# attenuator.net
KiCad netlist of a schematic drawn in Altium Designer
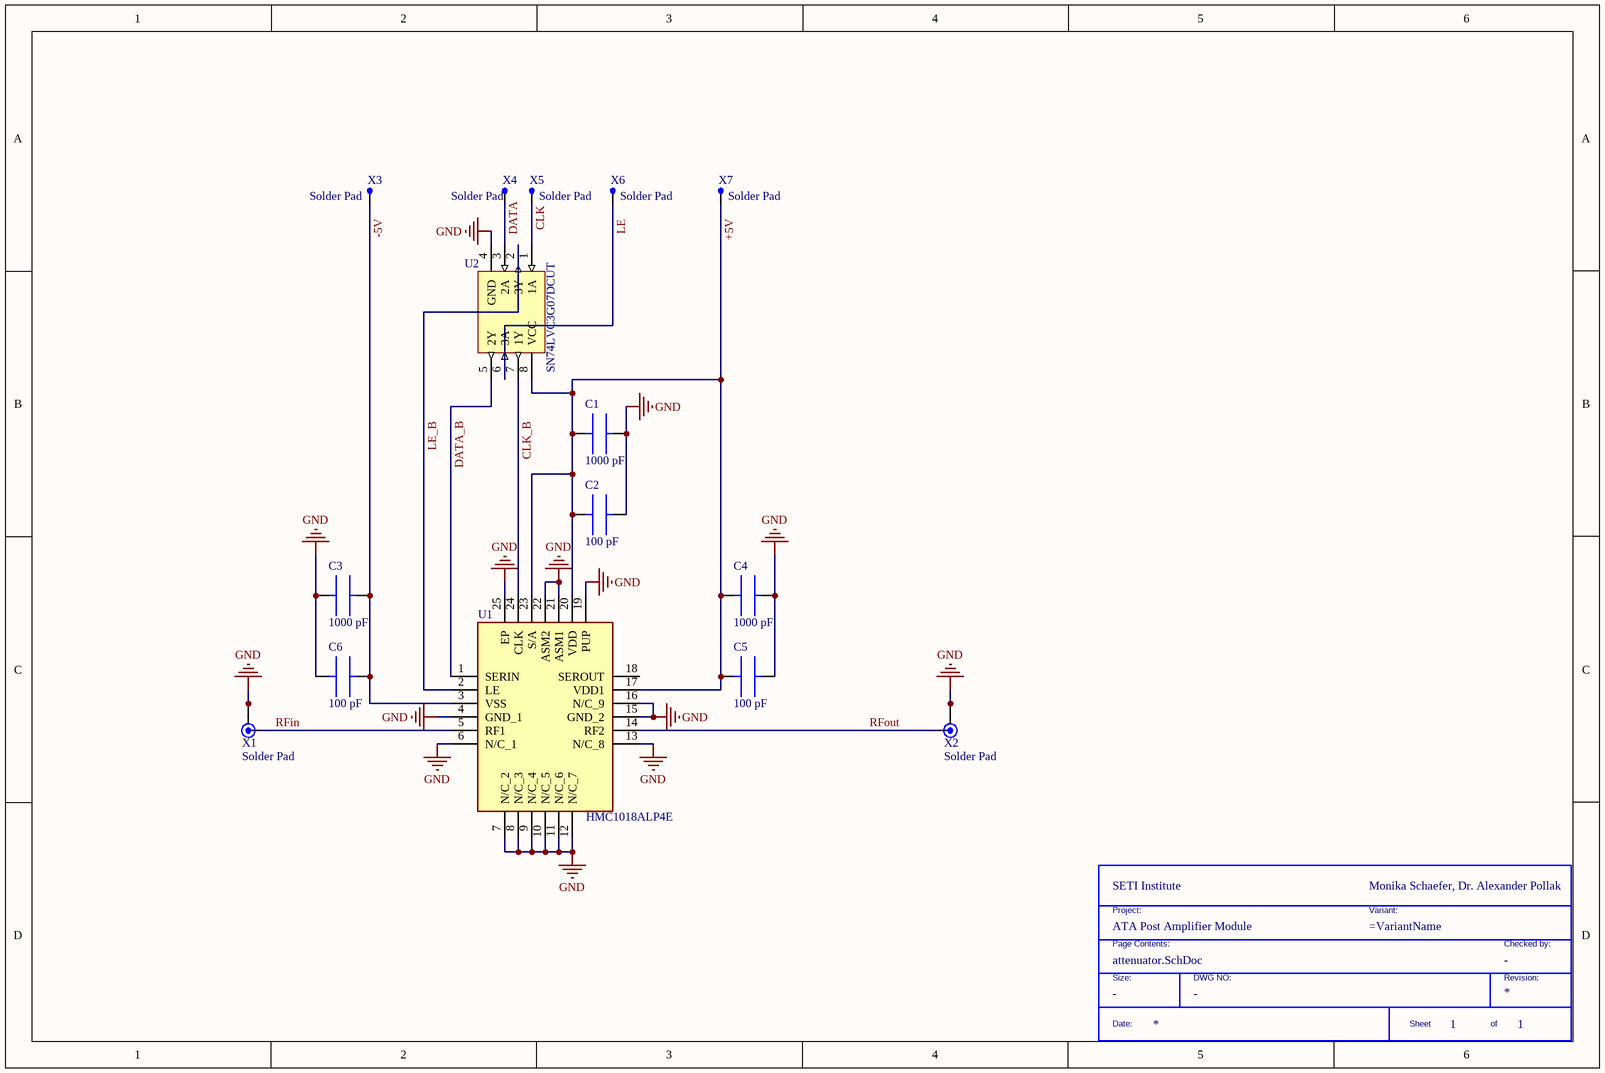
[diagram p0: attenuator.SchDoc]

(export (version "E")
  (design (tool "Eeschema 10.0.6"))
  (components
    (comp (ref "*")
      (value "TitleBlock")
      (description "Standard Title Block")
      (fields (field (name "DWG NO") "-") (field (name "SIZE") "-") (field (name "CHECKED BY") "-"))
      (libsource (lib "amp") (part "TitleBlock"))
    )
    (comp (ref "C1")
      (value "1000 pF")
      (footprint "C1000pF__C100nF")
      (fields
        (field (name "MANUFACTURER") "Murata")
        (field (name "MANUFACTURER PART NUMBER") "GCM1885C1H102FA16D")
      )
      (libsource (lib "attenuator") (part "C1000pF_GCM1885C1H102FA16D"))
    )
    (comp (ref "C2")
      (value "100 pF")
      (footprint "C100pF")
      (description "Multilayer Ceramic Capacitors MLCC - SMD/SMT 100 pF 100 VDC 1% 0402 C0G (NP0)")
      (fields
        (field (name "MANUFACTURER") "Murata")
        (field (name "MANUFACTURER PART NUMBER") "GRM1555C2A101FA01D")
      )
      (libsource (lib "attenuator") (part "C100pF_GRM1555C2A101FA01D"))
    )
    (comp (ref "C3")
      (value "1000 pF")
      (footprint "C1000pF__C100nF")
      (fields
        (field (name "MANUFACTURER") "Murata")
        (field (name "MANUFACTURER PART NUMBER") "GCM1885C1H102FA16D")
      )
      (libsource (lib "attenuator") (part "C1000pF_GCM1885C1H102FA16D"))
    )
    (comp (ref "C4")
      (value "1000 pF")
      (footprint "C1000pF__C100nF")
      (fields
        (field (name "MANUFACTURER") "Murata")
        (field (name "MANUFACTURER PART NUMBER") "GCM1885C1H102FA16D")
      )
      (libsource (lib "attenuator") (part "C1000pF_GCM1885C1H102FA16D"))
    )
    (comp (ref "C5")
      (value "100 pF")
      (footprint "C100pF")
      (description "Multilayer Ceramic Capacitors MLCC - SMD/SMT 100 pF 100 VDC 1% 0402 C0G (NP0)")
      (fields
        (field (name "MANUFACTURER") "Murata")
        (field (name "MANUFACTURER PART NUMBER") "GRM1555C2A101FA01D")
      )
      (libsource (lib "attenuator") (part "C100pF_GRM1555C2A101FA01D"))
    )
    (comp (ref "C6")
      (value "100 pF")
      (footprint "C100pF")
      (description "Multilayer Ceramic Capacitors MLCC - SMD/SMT 100 pF 100 VDC 1% 0402 C0G (NP0)")
      (fields
        (field (name "MANUFACTURER") "Murata")
        (field (name "MANUFACTURER PART NUMBER") "GRM1555C2A101FA01D")
      )
      (libsource (lib "attenuator") (part "C100pF_GRM1555C2A101FA01D"))
    )
    (comp (ref "U1")
      (value "HMC1018ALP4E")
      (footprint "Att_HMC101018ALPE")
      (description "Attenuators Attenuators")
      (fields (field (name "MOUSER PART NUMBER") "584-HMC1018ALP4E"))
      (libsource (lib "attenuator") (part "Att_HMC1018ALP4E"))
    )
    (comp (ref "U2")
      (value "SN74LVC3G07DCUT")
      (footprint "Buf_SN74LVC3G07DCUT")
      (description "Buffer, LVC/LCX/Z Series, 3-Func, 1-Input, CMOS, PDSO8")
      (fields (field (name "MANUFACTURER") "Texas Instruments"))
      (libsource (lib "attenuator") (part "Buf_SN74LVC3G07DCUT"))
    )
    (comp (ref "X1")
      (value "Solder Pad")
      (footprint "CPW Edge Connector")
      (description "Solder pad for RF Coplanar Waveguide Rogers 4350B Thickness 0.020\" Copper 1oz")
      (libsource (lib "amp") (part "RF  CPW Solder Pad"))
    )
    (comp (ref "X2")
      (value "Solder Pad")
      (footprint "CPW Edge Connector")
      (description "Solder pad for RF Coplanar Waveguide Rogers 4350B Thickness 0.020\" Copper 1oz")
      (libsource (lib "amp") (part "RF  CPW Solder Pad"))
    )
    (comp (ref "X3")
      (value "Solder Pad")
      (footprint "Solder Pad")
      (description "Pad to solder wires to")
      (libsource (lib "attenuator") (part "Solder Pad"))
    )
    (comp (ref "X4")
      (value "Solder Pad")
      (footprint "Solder Pad")
      (description "Pad to solder wires to")
      (libsource (lib "attenuator") (part "Solder Pad"))
    )
    (comp (ref "X5")
      (value "Solder Pad")
      (footprint "Solder Pad")
      (description "Pad to solder wires to")
      (libsource (lib "attenuator") (part "Solder Pad"))
    )
    (comp (ref "X6")
      (value "Solder Pad")
      (footprint "Solder Pad")
      (description "Pad to solder wires to")
      (libsource (lib "attenuator") (part "Solder Pad"))
    )
    (comp (ref "X7")
      (value "Solder Pad")
      (footprint "Solder Pad")
      (description "Pad to solder wires to")
      (libsource (lib "amp") (part "Solder Pad"))
    )
  )
  (nets
    (net (code "1") (name "/+5V") (class "Default")
      (node (ref "C1") (pin "1") (pinfunction "1_1") (pintype "passive"))
      (node (ref "C2") (pin "1") (pinfunction "1_1") (pintype "passive"))
      (node (ref "C4") (pin "1") (pinfunction "1_1") (pintype "passive"))
      (node (ref "C5") (pin "1") (pinfunction "1_1") (pintype "passive"))
      (node (ref "U1") (pin "17") (pinfunction "VDD1_17") (pintype "passive"))
      (node (ref "U1") (pin "20") (pinfunction "VDD_20") (pintype "passive"))
      (node (ref "U1") (pin "23") (pinfunction "S/A_23") (pintype "passive"))
      (node (ref "U2") (pin "8") (pinfunction "VCC_8") (pintype "passive"))
      (node (ref "X7") (pin "1") (pinfunction "1_1") (pintype "passive"))
    )
    (net (code "2") (name "/-5V") (class "Default")
      (node (ref "C3") (pin "2") (pinfunction "2_2") (pintype "passive"))
      (node (ref "C6") (pin "2") (pinfunction "2_2") (pintype "passive"))
      (node (ref "U1") (pin "3") (pinfunction "VSS_3") (pintype "passive"))
      (node (ref "X3") (pin "1") (pinfunction "1_1") (pintype "passive"))
    )
    (net (code "3") (name "/CLK") (class "Default")
      (node (ref "U2") (pin "1") (pinfunction "1A_1") (pintype "input"))
      (node (ref "X5") (pin "1") (pinfunction "1_1") (pintype "passive"))
    )
    (net (code "4") (name "/CLK_B") (class "Default")
      (node (ref "U1") (pin "24") (pinfunction "CLK_24") (pintype "passive"))
      (node (ref "U2") (pin "7") (pinfunction "1Y_7") (pintype "output"))
    )
    (net (code "5") (name "/DATA") (class "Default")
      (node (ref "U2") (pin "3") (pinfunction "2A_3") (pintype "input"))
      (node (ref "X4") (pin "1") (pinfunction "1_1") (pintype "passive"))
    )
    (net (code "6") (name "/DATA_B") (class "Default")
      (node (ref "U1") (pin "1") (pinfunction "SERIN_1") (pintype "passive"))
      (node (ref "U2") (pin "5") (pinfunction "2Y_5") (pintype "output"))
    )
    (net (code "7") (name "/LE") (class "Default")
      (node (ref "U2") (pin "6") (pinfunction "3A_6") (pintype "input"))
      (node (ref "X6") (pin "1") (pinfunction "1_1") (pintype "passive"))
    )
    (net (code "8") (name "/LE_B") (class "Default")
      (node (ref "U1") (pin "2") (pinfunction "LE_2") (pintype "passive"))
      (node (ref "U2") (pin "2") (pinfunction "3Y_2") (pintype "output"))
    )
    (net (code "9") (name "/RFin") (class "Default")
      (node (ref "U1") (pin "5") (pinfunction "RF1_5") (pintype "passive"))
      (node (ref "X1") (pin "1") (pinfunction "1_1") (pintype "passive"))
    )
    (net (code "10") (name "/RFout") (class "Default")
      (node (ref "U1") (pin "14") (pinfunction "RF2_14") (pintype "passive"))
      (node (ref "X2") (pin "1") (pinfunction "1_1") (pintype "passive"))
    )
    (net (code "11") (name "GND") (class "Default")
      (node (ref "C1") (pin "2") (pinfunction "2_2") (pintype "passive"))
      (node (ref "C2") (pin "2") (pinfunction "2_2") (pintype "passive"))
      (node (ref "C3") (pin "1") (pinfunction "1_1") (pintype "passive"))
      (node (ref "C4") (pin "2") (pinfunction "2_2") (pintype "passive"))
      (node (ref "C5") (pin "2") (pinfunction "2_2") (pintype "passive"))
      (node (ref "C6") (pin "1") (pinfunction "1_1") (pintype "passive"))
      (node (ref "U1") (pin "10") (pinfunction "N/C_5_10") (pintype "passive"))
      (node (ref "U1") (pin "11") (pinfunction "N/C_6_11") (pintype "passive"))
      (node (ref "U1") (pin "12") (pinfunction "N/C_7_12") (pintype "passive"))
      (node (ref "U1") (pin "13") (pinfunction "N/C_8_13") (pintype "passive"))
      (node (ref "U1") (pin "15") (pinfunction "GND_2_15") (pintype "passive"))
      (node (ref "U1") (pin "16") (pinfunction "N/C_9_16") (pintype "passive"))
      (node (ref "U1") (pin "19") (pinfunction "PUP_19") (pintype "passive"))
      (node (ref "U1") (pin "21") (pinfunction "ASM1_21") (pintype "passive"))
      (node (ref "U1") (pin "22") (pinfunction "ASM2_22") (pintype "passive"))
      (node (ref "U1") (pin "25") (pinfunction "EP_25") (pintype "passive"))
      (node (ref "U1") (pin "4") (pinfunction "GND_1_4") (pintype "passive"))
      (node (ref "U1") (pin "6") (pinfunction "N/C_1_6") (pintype "passive"))
      (node (ref "U1") (pin "7") (pinfunction "N/C_2_7") (pintype "passive"))
      (node (ref "U1") (pin "8") (pinfunction "N/C_3_8") (pintype "passive"))
      (node (ref "U1") (pin "9") (pinfunction "N/C_4_9") (pintype "passive"))
      (node (ref "U2") (pin "4") (pinfunction "GND_4") (pintype "passive"))
      (node (ref "X1") (pin "2") (pinfunction "2_2") (pintype "passive"))
      (node (ref "X1") (pin "3") (pinfunction "3_3") (pintype "passive"))
      (node (ref "X2") (pin "2") (pinfunction "2_2") (pintype "passive"))
      (node (ref "X2") (pin "3") (pinfunction "3_3") (pintype "passive"))
    )
    (net (code "12") (name "unconnected-(U1-SEROUT-Pad18)") (class "Default")
      (node (ref "U1") (pin "18") (pinfunction "SEROUT_18") (pintype "passive"))
    )
  )
)
